# 07_DEBUG.net
KiCad netlist of a schematic drawn in Altium Designer
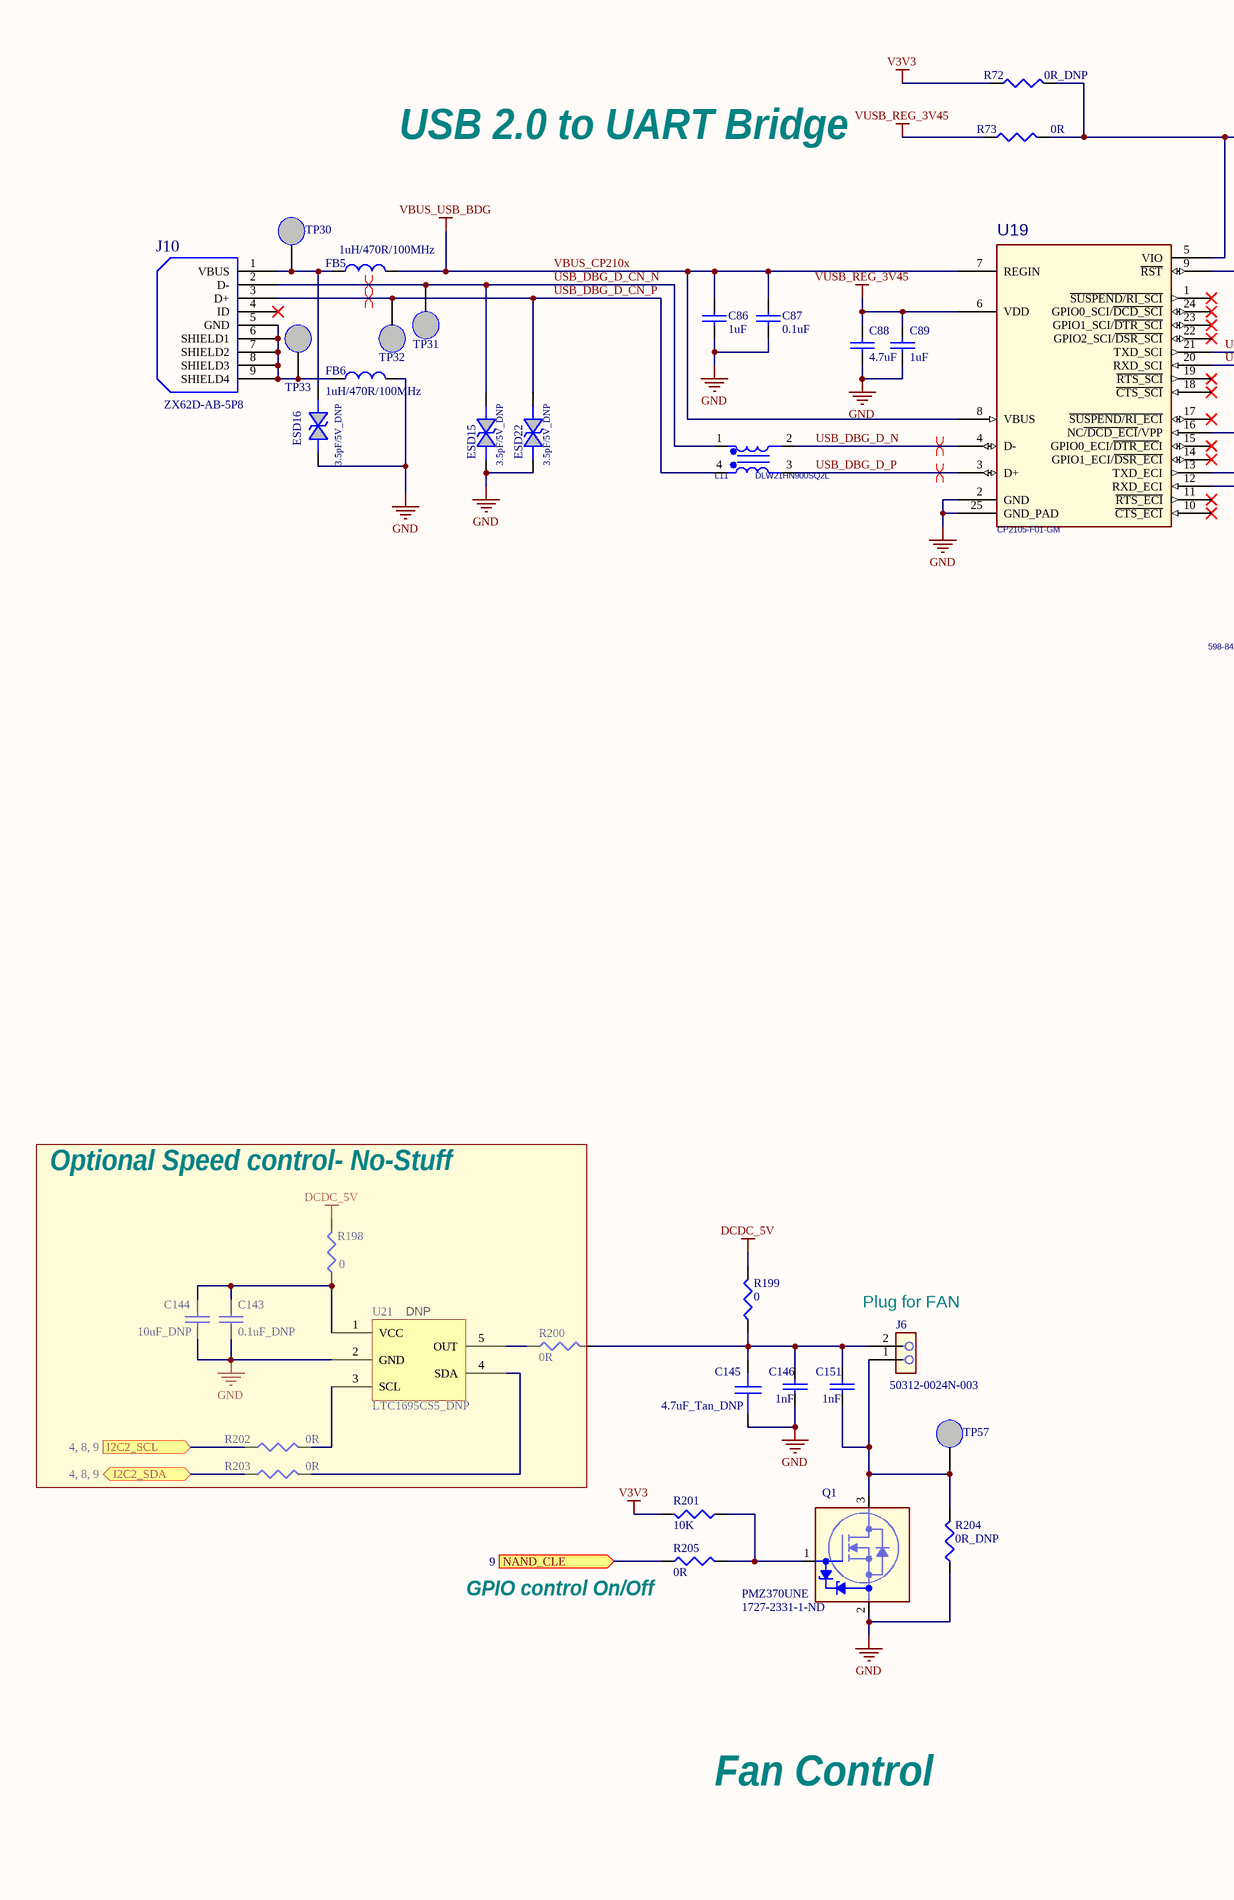
[diagram p0: 07_DEBUG.SchDoc, left]
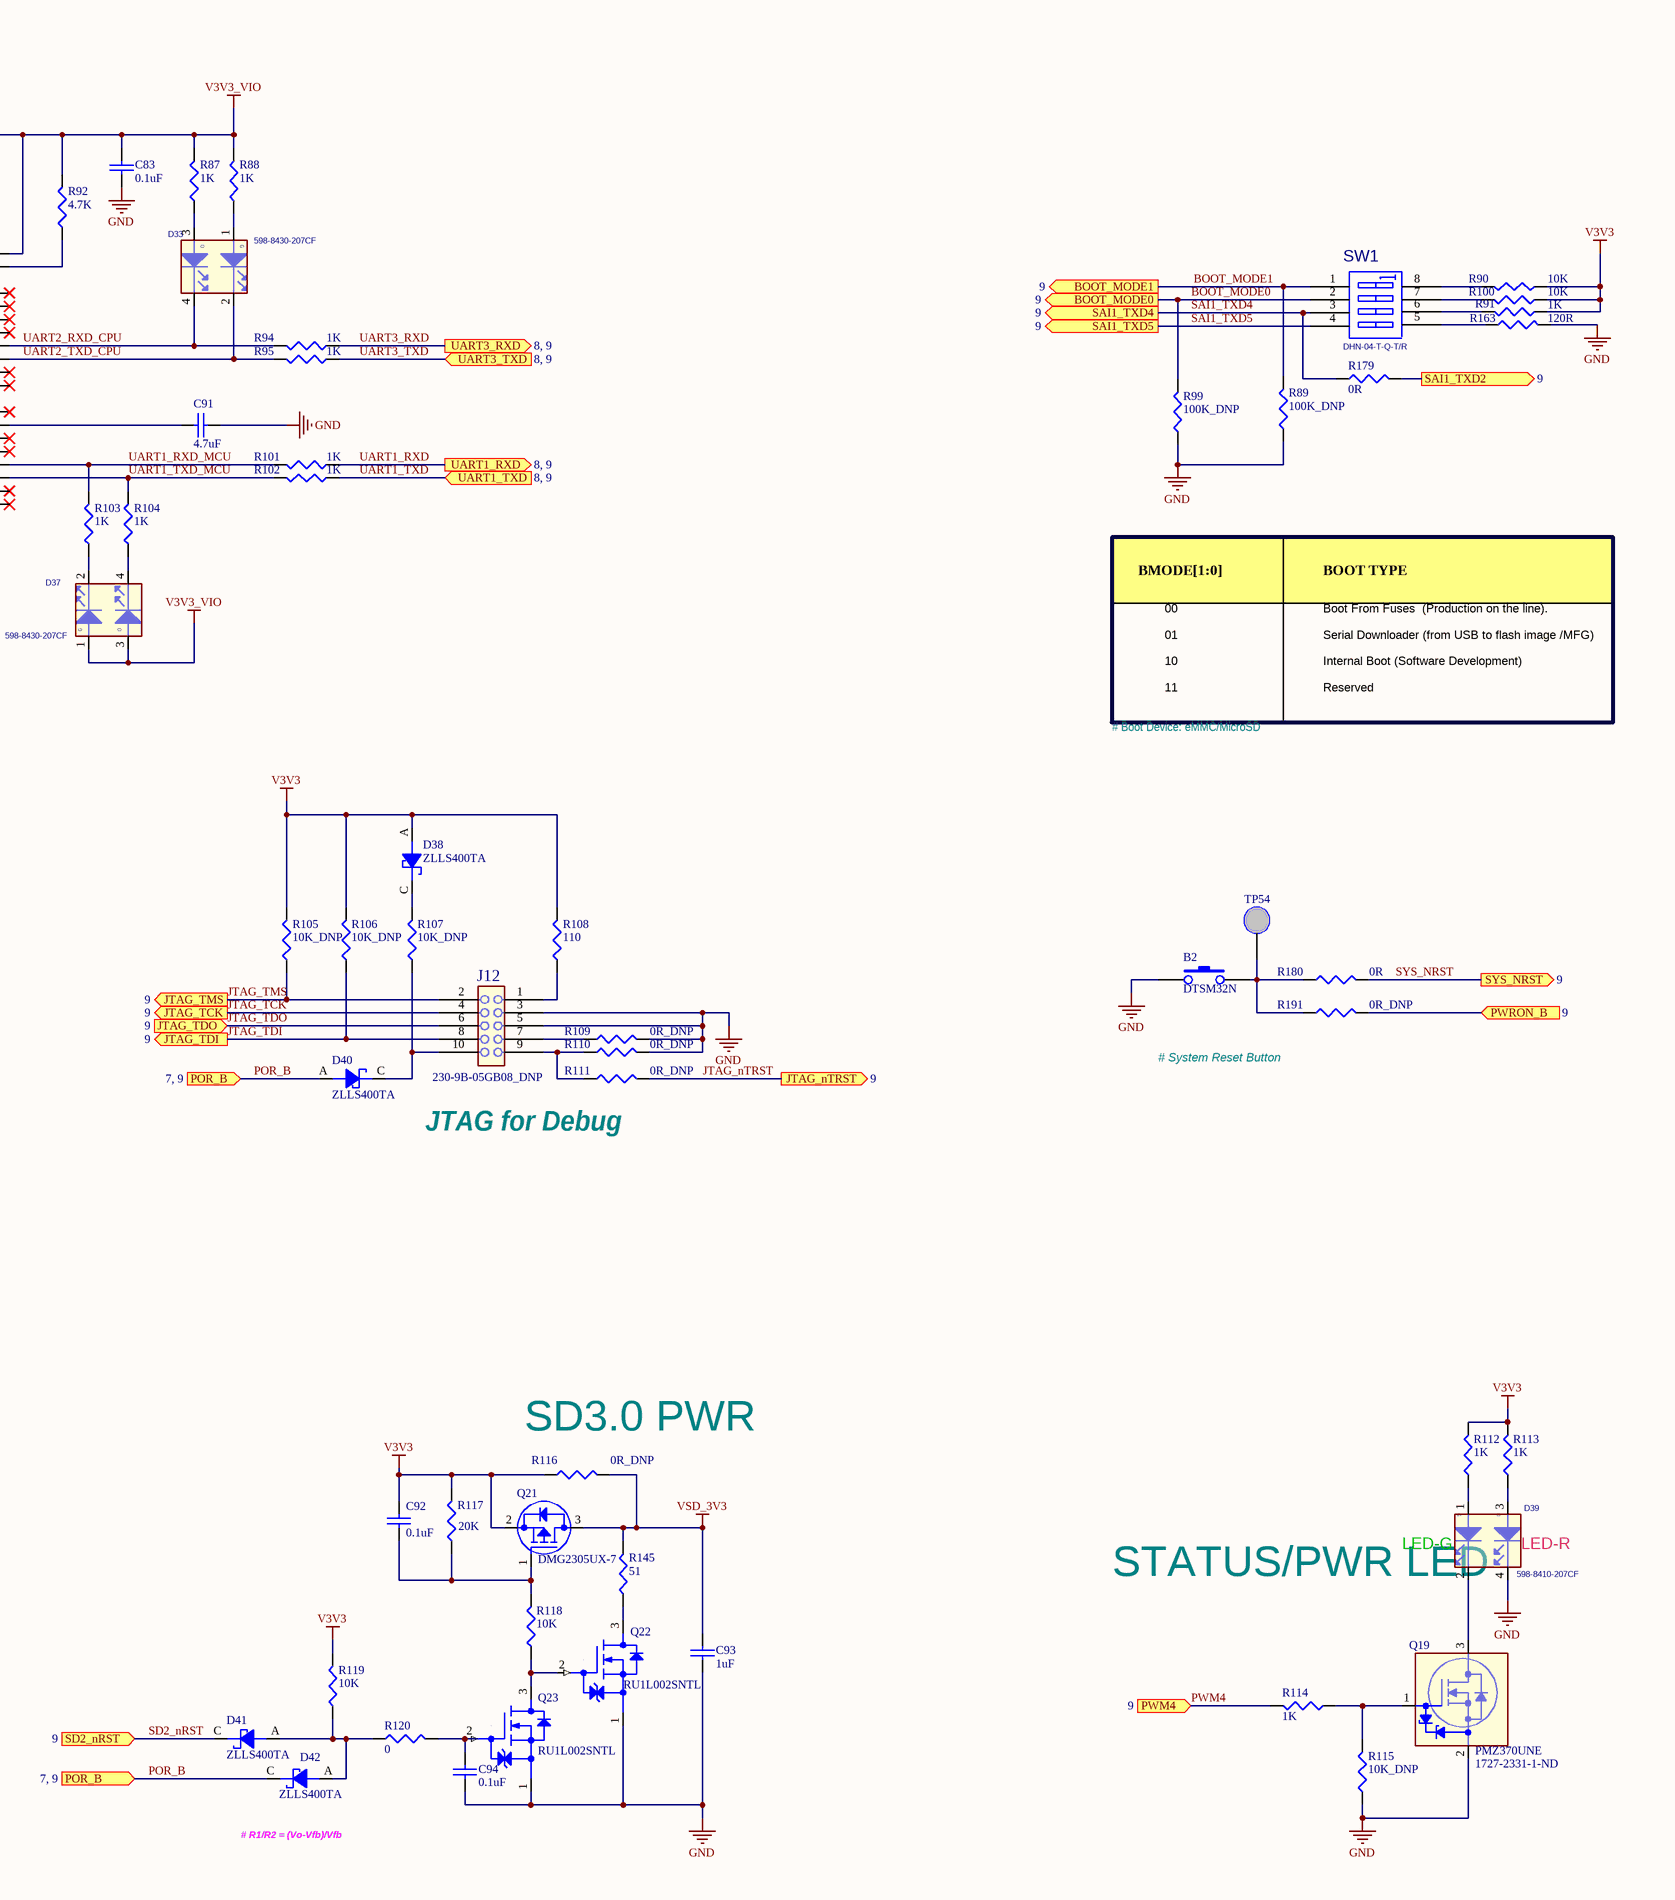
[diagram p1: 07_DEBUG.SchDoc, right]

(export (version "E")
  (design (tool "Eeschema 10.0.6"))
  (components
    (comp (ref "B2")
      (value "DTSM32N")
      (footprint "sw2-6_0x3_5-h5_2")
      (description "Tact Switch")
      (fields (field (name "MPN") "DTSM-32N-Q-TR"))
      (libsource (lib "links") (part "SW-PB"))
    )
    (comp (ref "C83")
      (value "0.1uF")
      (footprint "0201")
      (description "CAP CER 0.1UF 10V 10% X5R 0201")
      (fields (field (name "MPN") "C0603X5R1A104K030BC") (field (name "Comment") "0.1uF/10V"))
      (libsource (lib "links") (part "CAP_0201_0.1uF"))
    )
    (comp (ref "C86")
      (value "1uF")
      (footprint "0201")
      (description "CAP CER 1UF 6.3V 20% X5R 0201")
      (fields (field (name "MPN") "C0603X5R0J105M030BC") (field (name "Comment") "1uF/6.3V"))
      (libsource (lib "links") (part "CAP_0201_1.0uF"))
    )
    (comp (ref "C87")
      (value "0.1uF")
      (footprint "0201")
      (description "CAP CER 0.1UF 10V 10% X5R 0201")
      (fields (field (name "MPN") "C0603X5R1A104K030BC") (field (name "Comment") "0.1uF/10V"))
      (libsource (lib "links") (part "CAP_0201_0.1uF"))
    )
    (comp (ref "C88")
      (value "4.7uF")
      (footprint "0402")
      (description "CAP CER 4.7UF 10V 20% X5R 0402")
      (fields (field (name "MPN") "C1005X5R1A475M050BC") (field (name "Comment") "4.7uF/10V"))
      (libsource (lib "links") (part "CAP_0402_4.7uF"))
    )
    (comp (ref "C89")
      (value "1uF")
      (footprint "0201")
      (description "CAP CER 1UF 6.3V 20% X5R 0201")
      (fields (field (name "MPN") "C0603X5R0J105M030BC") (field (name "Comment") "1uF/6.3V"))
      (libsource (lib "links") (part "CAP_0201_1.0uF"))
    )
    (comp (ref "C91")
      (value "4.7uF")
      (footprint "0402")
      (description "CAP CER 4.7UF 10V 20% X5R 0402")
      (fields (field (name "MPN") "C1005X5R1A475M050BC") (field (name "Comment") "4.7uF/10V"))
      (libsource (lib "links") (part "CAP_0402_4.7uF"))
    )
    (comp (ref "C92")
      (value "0.1uF")
      (footprint "0201")
      (description "CAP CER 0.1UF 10V 10% X5R 0201")
      (fields (field (name "MPN") "C0603X5R1A104K030BC") (field (name "Comment") "0.1uF/10V"))
      (libsource (lib "links") (part "CAP_0201_0.1uF"))
    )
    (comp (ref "C93")
      (value "1uF")
      (footprint "0201")
      (description "CAP CER 1UF 6.3V 20% X5R 0201")
      (fields (field (name "MPN") "C0603X5R0J105M030BC") (field (name "Comment") "1uF/6.3V"))
      (libsource (lib "links") (part "CAP_0201_1.0uF"))
    )
    (comp (ref "C94")
      (value "0.1uF")
      (footprint "0201")
      (description "CAP CER 0.1UF 10V 10% X5R 0201")
      (fields (field (name "MPN") "C0603X5R1A104K030BC") (field (name "Comment") "0.1uF/10V"))
      (libsource (lib "links") (part "CAP_0201_0.1uF"))
    )
    (comp (ref "C143")
      (value "0.1uF_DNP")
      (footprint "0201")
      (description "CAP CER 0.1UF 10V 10% X5R 0201")
      (fields (field (name "MPN") "C0603X5R1A104K030BC") (field (name "Comment") "0.1uF/10V"))
      (libsource (lib "links") (part "CAP_0201_0.1uF"))
    )
    (comp (ref "C144")
      (value "10uF_DNP")
      (footprint "0402")
      (description "CAP CER 10UF 10V 20% X5R 0402")
      (fields (field (name "MPN") "CL05A106MP5NUNC") (field (name "Comment") "10uF/10V"))
      (libsource (lib "links") (part "CAP_0402_10uF"))
    )
    (comp (ref "C145")
      (value "4.7uF_Tan_DNP")
      (footprint "1206")
      (description "CAP CER 47UF 25V 20% 1206")
      (fields (field (name "MPN") "C3216JB1E476M160AC") (field (name "Comment") "47uF/25V"))
      (libsource (lib "links") (part "CAP_1206_47uF_25V"))
    )
    (comp (ref "C146")
      (value "1nF")
      (footprint "0201")
      (description "CAP CER 1nF 25V 10% X7R 0201")
      (fields (field (name "MPN") "GRM033R71E102KA01D") (field (name "Comment") "1nF/25V"))
      (libsource (lib "links") (part "CAP_0201_1.0nF"))
    )
    (comp (ref "C151")
      (value "1nF")
      (footprint "0201")
      (description "CAP CER 1nF 25V 10% X7R 0201")
      (fields (field (name "MPN") "GRM033R71E102KA01D") (field (name "Comment") "1nF/25V"))
      (libsource (lib "links") (part "CAP_0201_1.0nF"))
    )
    (comp (ref "D33")
      (value "598-8430-207CF")
      (footprint "LED_0606")
      (description "LED BI-COLOR ORANGE/GRN 20MA SMD 0606")
      (libsource (lib "") (part "LED4_DUAL_OG_1"))
    )
    (comp (ref "D37")
      (value "598-8430-207CF")
      (footprint "LED_0606")
      (description "LED BI-COLOR ORANGE/GRN 20MA SMD 0606")
      (libsource (lib "SpacePark") (part "LED4_DUAL_OG"))
    )
    (comp (ref "D38")
      (value "ZLLS400TA")
      (footprint "SOD323")
      (description "DIODE SCHOTTKY 40V 520MA SOD323")
      (libsource (lib "SpacePark") (part "DIODE_SCHTKY"))
    )
    (comp (ref "D39")
      (value "598-8410-207CF")
      (footprint "LED_0606")
      (description "LED BI-COLOR ORANGE/GRN 20MA SMD 0606")
      (fields (field (name "MPN") "598-8430-207CF"))
      (libsource (lib "") (part "LED4_DUAL_OG_2"))
    )
    (comp (ref "D40")
      (value "ZLLS400TA")
      (footprint "SOD323")
      (description "DIODE SCHOTTKY 40V 520MA SOD323")
      (libsource (lib "SpacePark") (part "DIODE_SCHTKY"))
    )
    (comp (ref "D41")
      (value "ZLLS400TA")
      (footprint "SOD323")
      (description "DIODE SCHOTTKY 40V 520MA SOD323")
      (libsource (lib "SpacePark") (part "DIODE_SCHTKY"))
    )
    (comp (ref "D42")
      (value "ZLLS400TA")
      (footprint "SOD323")
      (description "DIODE SCHOTTKY 40V 520MA SOD323")
      (libsource (lib "SpacePark") (part "DIODE_SCHTKY"))
    )
    (comp (ref "ESD15")
      (value "3.5pF/5V_DNP")
      (footprint "0201")
      (description "DIODE TVS 15kV 10V 50A 8pF SMT RoHS")
      (fields (field (name "MPN") "DESD5V0V1BCSP-7"))
      (libsource (lib "links") (part "DIODE BI-DIR TRIG"))
    )
    (comp (ref "ESD16")
      (value "3.5pF/5V_DNP")
      (footprint "0201")
      (description "DIODE TVS 15kV 10V 50A 8pF SMT RoHS")
      (fields (field (name "MPN") "DESD5V0V1BCSP-7"))
      (libsource (lib "links") (part "DIODE BI-DIR TRIG"))
    )
    (comp (ref "ESD22")
      (value "3.5pF/5V_DNP")
      (footprint "0201")
      (description "DIODE TVS 15kV 10V 50A 8pF SMT RoHS")
      (fields (field (name "MPN") "DESD5V0V1BCSP-7"))
      (libsource (lib "links") (part "DIODE BI-DIR TRIG"))
    )
    (comp (ref "FB5")
      (value "1uH/470R/100MHz")
      (footprint "0603")
      (description "FERRITE CHIP 470 OHM 1.0A 0603")
      (fields (field (name "MPN") "BLM18PG471SN1"))
      (libsource (lib "links") (part "INDUCTOR_BLM18PG471SN1"))
    )
    (comp (ref "FB6")
      (value "1uH/470R/100MHz")
      (footprint "0603")
      (description "FERRITE CHIP 470 OHM 1.0A 0603")
      (fields (field (name "MPN") "BLM18PG471SN1"))
      (libsource (lib "links") (part "INDUCTOR_BLM18PG471SN1"))
    )
    (comp (ref "J6")
      (value "50312-0024N-003")
      (footprint "SIP2-2MM-6X4_8MM-50312")
      (description "CONN DIP HEADER 2P 1R MS(P2.0,H6.2)")
      (libsource (lib "SBC") (part "HEADER 1X2"))
    )
    (comp (ref "J10")
      (value "ZX62D-AB-5P8")
      (footprint "USB5-0_65-ZX62D-AB-5P8")
      (description "Micro USB AB Connector, Standard SMT + DIP")
      (libsource (lib "links") (part "USB_AB"))
    )
    (comp (ref "J12")
      (value "230-9B-05GB08_DNP")
      (footprint "HD2X5-1_27MM-3_35MM")
      (description "2x5 pin header, 1.27mm pitch, THM")
      (fields (field (name "MPN") "230-9B-05GB08"))
      (libsource (lib "links") (part "HEADER 2x5"))
    )
    (comp (ref "L11")
      (value "DLW21HN900SQ2L")
      (footprint "IND4_CHOKE_0805")
      (description "IND CHK 90 OHM@100MHZ 330MA 25% 0805")
      (libsource (lib "SpacePark") (part "IND_CMC_DLW21"))
    )
    (comp (ref "Q1")
      (value "PMZ370UNE")
      (footprint "DFN10106B")
      (description "N-Channel 30V 590mA, SMT DFN1006B-3")
      (fields (field (name "SUPPLIER PART NUMBER 1") "1727-2331-1-ND") (field (name "MPN") "PMZB550UNEYL"))
      (libsource (lib "SpacePark") (part "NMOS_NX3008NBK"))
    )
    (comp (ref "Q19")
      (value "PMZ370UNE")
      (footprint "DFN10106B")
      (description "N-Channel 30V 590mA, SMT DFN1006B-3")
      (fields (field (name "SUPPLIER PART NUMBER 1") "1727-2331-1-ND") (field (name "MPN") "PMZB550UNEYL"))
      (libsource (lib "SpacePark") (part "NMOS_NX3008NBK"))
    )
    (comp (ref "Q21")
      (value "DMG2305UX-7")
      (footprint "SOT-23")
      (description "P-Channel 20V 4.2A (Ta) 1.4W (Ta) Surface Mount SOT-23")
      (libsource (lib "SpacePark") (part "MOSFET_P"))
    )
    (comp (ref "Q22")
      (value "RU1L002SNTL")
      (footprint "SOT323_3")
      (description "N-Channel 30V 100mA (Ta) 200mW (Ta) Surface Mount SOT-323")
      (fields (field (name "MPN") "SOT323_3"))
      (libsource (lib "SpacePark") (part "2SK3018"))
    )
    (comp (ref "Q23")
      (value "RU1L002SNTL")
      (footprint "SOT323_3")
      (description "N-Channel 30V 100mA (Ta) 200mW (Ta) Surface Mount SOT-323")
      (fields (field (name "MPN") "SOT323_3"))
      (libsource (lib "SpacePark") (part "2SK3018"))
    )
    (comp (ref "R72")
      (value "0R_DNP")
      (footprint "0201")
      (description "RES SMD 0.0OHM JUMPER 1/20W 0201")
      (fields (field (name "MPN") "ERJ-1GN0R00C"))
      (libsource (lib "links") (part "R_0201_0"))
    )
    (comp (ref "R73")
      (value "0R")
      (footprint "0201")
      (description "RES SMD 0.0OHM JUMPER 1/20W 0201")
      (fields (field (name "MPN") "ERJ-1GN0R00C"))
      (libsource (lib "links") (part "R_0201_0"))
    )
    (comp (ref "R87")
      (value "1K")
      (footprint "0201")
      (description "RES SMD 1K OHM 1% 1/20W 0201")
      (fields (field (name "MPN") "ERJ-1GEF1001C") (field (name "Comment") "1K/1%"))
      (libsource (lib "links") (part "R_0201_1K"))
    )
    (comp (ref "R88")
      (value "1K")
      (footprint "0201")
      (description "RES SMD 1K OHM 1% 1/20W 0201")
      (fields (field (name "MPN") "ERJ-1GEF1001C") (field (name "Comment") "1K/1%"))
      (libsource (lib "links") (part "R_0201_1K"))
    )
    (comp (ref "R89")
      (value "100K_DNP")
      (footprint "0201")
      (description "RES SMD 100K OHM JUMPER 1/20W  0201")
      (fields (field (name "MPN") "ERJ-1GEF1003C"))
      (libsource (lib "links") (part "R_0201_100K"))
    )
    (comp (ref "R90")
      (value "10K")
      (footprint "0201")
      (description "RES SMD 10K OHM JUMPER 1/20W  0201")
      (fields (field (name "MPN") "ERJ-1GEF103C"))
      (libsource (lib "links") (part "R_0201_10K"))
    )
    (comp (ref "R91")
      (value "1K")
      (footprint "0201")
      (description "RES SMD 1K OHM 1% 1/20W 0201")
      (fields (field (name "MPN") "ERJ-1GEF1001C") (field (name "Comment") "1K/1%"))
      (libsource (lib "links") (part "R_0201_1K"))
    )
    (comp (ref "R92")
      (value "4.7K")
      (footprint "0201")
      (description "RES SMD 4.7K OHM 1% 1/20W 0201")
      (fields (field (name "MPN") "ERJ-1GEF4701C"))
      (libsource (lib "links") (part "R_0201_4.7K"))
    )
    (comp (ref "R94")
      (value "1K")
      (footprint "0201")
      (description "RES SMD 1K OHM 1% 1/20W 0201")
      (fields (field (name "MPN") "ERJ-1GEF1001C") (field (name "Comment") "1K/1%"))
      (libsource (lib "links") (part "R_0201_1K"))
    )
    (comp (ref "R95")
      (value "1K")
      (footprint "0201")
      (description "RES SMD 1K OHM 1% 1/20W 0201")
      (fields (field (name "MPN") "ERJ-1GEF1001C") (field (name "Comment") "1K/1%"))
      (libsource (lib "links") (part "R_0201_1K"))
    )
    (comp (ref "R99")
      (value "100K_DNP")
      (footprint "0201")
      (description "RES SMD 100K OHM JUMPER 1/20W  0201")
      (fields (field (name "MPN") "ERJ-1GEF1003C"))
      (libsource (lib "links") (part "R_0201_100K"))
    )
    (comp (ref "R100")
      (value "10K")
      (footprint "0201")
      (description "RES SMD 10K OHM JUMPER 1/20W  0201")
      (fields (field (name "MPN") "ERJ-1GEF103C"))
      (libsource (lib "links") (part "R_0201_10K"))
    )
    (comp (ref "R101")
      (value "1K")
      (footprint "0201")
      (description "RES SMD 1K OHM 1% 1/20W 0201")
      (fields (field (name "MPN") "ERJ-1GEF1001C") (field (name "Comment") "1K/1%"))
      (libsource (lib "links") (part "R_0201_1K"))
    )
    (comp (ref "R102")
      (value "1K")
      (footprint "0201")
      (description "RES SMD 1K OHM 1% 1/20W 0201")
      (fields (field (name "MPN") "ERJ-1GEF1001C") (field (name "Comment") "1K/1%"))
      (libsource (lib "links") (part "R_0201_1K"))
    )
    (comp (ref "R103")
      (value "1K")
      (footprint "0201")
      (description "RES SMD 1K OHM 1% 1/20W 0201")
      (fields (field (name "MPN") "ERJ-1GEF1001C") (field (name "Comment") "1K/1%"))
      (libsource (lib "links") (part "R_0201_1K"))
    )
    (comp (ref "R104")
      (value "1K")
      (footprint "0201")
      (description "RES SMD 1K OHM 1% 1/20W 0201")
      (fields (field (name "MPN") "ERJ-1GEF1001C") (field (name "Comment") "1K/1%"))
      (libsource (lib "links") (part "R_0201_1K"))
    )
    (comp (ref "R105")
      (value "10K_DNP")
      (footprint "0201")
      (description "RES SMD 10K OHM JUMPER 1/20W  0201")
      (fields (field (name "MPN") "ERJ-1GEF103C"))
      (libsource (lib "links") (part "R_0201_10K"))
    )
    (comp (ref "R106")
      (value "10K_DNP")
      (footprint "0201")
      (description "RES SMD 10K OHM JUMPER 1/20W  0201")
      (fields (field (name "MPN") "ERJ-1GEF103C"))
      (libsource (lib "links") (part "R_0201_10K"))
    )
    (comp (ref "R107")
      (value "10K_DNP")
      (footprint "0201")
      (description "RES SMD 10K OHM JUMPER 1/20W  0201")
      (fields (field (name "MPN") "ERJ-1GEF103C"))
      (libsource (lib "links") (part "R_0201_10K"))
    )
    (comp (ref "R108")
      (value "110")
      (footprint "0201")
      (description "RES SMD 110 OHM 1% 1/20W 0201")
      (fields (field (name "MPN") "ERJ-1GEF1100C"))
      (libsource (lib "links") (part "R_0201_110"))
    )
    (comp (ref "R109")
      (value "0R_DNP")
      (footprint "0201")
      (description "RES SMD 0.0OHM JUMPER 1/20W 0201")
      (fields (field (name "MPN") "ERJ-1GN0R00C"))
      (libsource (lib "links") (part "R_0201_0"))
    )
    (comp (ref "R110")
      (value "0R_DNP")
      (footprint "0201")
      (description "RES SMD 0.0OHM JUMPER 1/20W 0201")
      (fields (field (name "MPN") "ERJ-1GN0R00C"))
      (libsource (lib "links") (part "R_0201_0"))
    )
    (comp (ref "R111")
      (value "0R_DNP")
      (footprint "0201")
      (description "RES SMD 0.0OHM JUMPER 1/20W 0201")
      (fields (field (name "MPN") "ERJ-1GN0R00C"))
      (libsource (lib "links") (part "R_0201_0"))
    )
    (comp (ref "R112")
      (value "1K")
      (footprint "0201")
      (description "RES SMD 1K OHM 1% 1/20W 0201")
      (fields (field (name "MPN") "ERJ-1GEF1001C") (field (name "Comment") "1K/1%"))
      (libsource (lib "links") (part "R_0201_1K"))
    )
    (comp (ref "R113")
      (value "1K")
      (footprint "0201")
      (description "RES SMD 1K OHM 1% 1/20W 0201")
      (fields (field (name "MPN") "ERJ-1GEF1001C") (field (name "Comment") "1K/1%"))
      (libsource (lib "links") (part "R_0201_1K"))
    )
    (comp (ref "R114")
      (value "1K")
      (footprint "0201")
      (description "RES SMD 1K OHM 1% 1/20W 0201")
      (fields (field (name "MPN") "ERJ-1GEF1001C") (field (name "Comment") "1K/1%"))
      (libsource (lib "links") (part "R_0201_1K"))
    )
    (comp (ref "R115")
      (value "10K_DNP")
      (footprint "0201")
      (description "RES SMD 10K OHM JUMPER 1/20W  0201")
      (fields (field (name "MPN") "ERJ-1GEF103C"))
      (libsource (lib "links") (part "R_0201_10K"))
    )
    (comp (ref "R116")
      (value "0R_DNP")
      (footprint "0402")
      (description "RES SMD 0.0 OHM JUMPER 1/10W  0402")
      (fields (field (name "MPN") "ERJ-2GE0R00X"))
      (libsource (lib "links") (part "R_0402_0"))
    )
    (comp (ref "R117")
      (value "20K")
      (footprint "0201")
      (description "RES SMD 20K OHM 1% 1/20W 0201")
      (fields (field (name "MPN") "ERJ-1GEF2002C"))
      (libsource (lib "links") (part "R_0201_20K"))
    )
    (comp (ref "R118")
      (value "10K")
      (footprint "0201")
      (description "RES SMD 10K OHM JUMPER 1/20W  0201")
      (fields (field (name "MPN") "ERJ-1GEF103C"))
      (libsource (lib "links") (part "R_0201_10K"))
    )
    (comp (ref "R119")
      (value "10K")
      (footprint "0201")
      (description "RES SMD 10K OHM JUMPER 1/20W  0201")
      (fields (field (name "MPN") "ERJ-1GEF103C"))
      (libsource (lib "links") (part "R_0201_10K"))
    )
    (comp (ref "R120")
      (value "0")
      (footprint "0402")
      (description "RES SMD 0.0 OHM JUMPER 1/10W  0402")
      (fields (field (name "MPN") "ERJ-2GE0R00X") (field (name "Comment") "0R"))
      (libsource (lib "links") (part "R_0402_0"))
    )
    (comp (ref "R145")
      (value "51")
      (footprint "0402")
      (description "RES SMD 51 OHM 1% 1/10W 0402")
      (fields (field (name "MPN") "ERJ-2RKF51R0X"))
      (libsource (lib "links") (part "R_0402_51"))
    )
    (comp (ref "R163")
      (value "120R")
      (footprint "0402")
      (description "RES SMD 120 OHM 1% 1/10W 0402")
      (fields (field (name "MPN") "RC0402FR-07120R"))
      (libsource (lib "links") (part "R_0402_120"))
    )
    (comp (ref "R179")
      (value "0R")
      (footprint "0201")
      (description "RES SMD 0.0OHM JUMPER 1/20W 0201")
      (fields (field (name "MPN") "ERJ-1GN0R00C"))
      (libsource (lib "links") (part "R_0805_0"))
    )
    (comp (ref "R180")
      (value "0R")
      (footprint "0201")
      (description "RES SMD 0.0OHM JUMPER 1/20W 0201")
      (fields (field (name "MPN") "ERJ-1GN0R00C") (field (name "Comment") "0R_DNP"))
      (libsource (lib "links") (part "R_0201_0"))
    )
    (comp (ref "R191")
      (value "0R_DNP")
      (footprint "0201")
      (description "RES SMD 0.0OHM JUMPER 1/20W 0201")
      (fields (field (name "MPN") "ERJ-1GN0R00C"))
      (libsource (lib "links") (part "R_0201_0"))
    )
    (comp (ref "R198")
      (value "0")
      (footprint "0402")
      (description "RES SMD 0.0 OHM JUMPER 1/10W  0402")
      (fields (field (name "MPN") "ERJ-2GE0R00X") (field (name "Comment") "0R"))
      (libsource (lib "links") (part "R_0402_0"))
    )
    (comp (ref "R199")
      (value "0")
      (footprint "0402")
      (description "RES SMD 0.0 OHM JUMPER 1/10W  0402")
      (fields (field (name "MPN") "ERJ-2GE0R00X") (field (name "Comment") "0R"))
      (libsource (lib "links") (part "R_0402_0"))
    )
    (comp (ref "R200")
      (value "0R")
      (footprint "0402")
      (description "RES SMD 0.0 OHM JUMPER 1/10W  0402")
      (fields (field (name "MPN") "ERJ-2GE0R00X"))
      (libsource (lib "links") (part "R_0402_0"))
    )
    (comp (ref "R201")
      (value "10K")
      (footprint "0201")
      (description "RES SMD 10K OHM JUMPER 1/20W  0201")
      (fields (field (name "MPN") "ERJ-1GEF103C"))
      (libsource (lib "links") (part "R_0201_10K"))
    )
    (comp (ref "R202")
      (value "0R")
      (footprint "0201")
      (description "RES SMD 0.0OHM JUMPER 1/20W 0201")
      (fields (field (name "MPN") "ERJ-1GN0R00C") (field (name "Comment") "0"))
      (libsource (lib "links") (part "R_0201_0"))
    )
    (comp (ref "R203")
      (value "0R")
      (footprint "0201")
      (description "RES SMD 0.0OHM JUMPER 1/20W 0201")
      (fields (field (name "MPN") "ERJ-1GN0R00C") (field (name "Comment") "0"))
      (libsource (lib "links") (part "R_0201_0"))
    )
    (comp (ref "R204")
      (value "0R_DNP")
      (footprint "0402")
      (description "RES SMD 0.0 OHM JUMPER 1/10W  0402")
      (fields (field (name "MPN") "ERJ-2GE0R00X") (field (name "Comment") "0R"))
      (libsource (lib "links") (part "R_0402_0"))
    )
    (comp (ref "R205")
      (value "0R")
      (footprint "0201")
      (description "RES SMD 0.0OHM JUMPER 1/20W 0201")
      (fields (field (name "MPN") "ERJ-1GN0R00C") (field (name "Comment") "0R_DNP"))
      (libsource (lib "links") (part "R_0201_0"))
    )
    (comp (ref "SW1")
      (value "DHN-04-T-Q-T/R")
      (footprint "SW_DIP4_SM")
      (description "SW 4P SPST DIP 25MA 24V SMT")
      (libsource (lib "SpacePark") (part "SW_DIP-4"))
    )
    (comp (ref "TP30")
      (value "TP NM")
      (footprint "TP_SMD_L")
      (description "TEST POINT (Large)")
      (libsource (lib "links") (part "TP_L"))
    )
    (comp (ref "TP31")
      (value "TP NM")
      (footprint "TP_SMD")
      (description "TEST POIN")
      (libsource (lib "links") (part "TP"))
    )
    (comp (ref "TP32")
      (value "TP NM")
      (footprint "TP_SMD")
      (description "TEST POIN")
      (libsource (lib "links") (part "TP"))
    )
    (comp (ref "TP33")
      (value "TP NM")
      (footprint "TP_SMD_L")
      (description "TEST POINT (Large)")
      (libsource (lib "links") (part "TP_L"))
    )
    (comp (ref "TP54")
      (value "TP NM")
      (footprint "TP_SMD_L")
      (description "TEST POINT (Large)")
      (libsource (lib "links") (part "TP_L"))
    )
    (comp (ref "TP57")
      (value "TP NM")
      (footprint "TP_SMD_L")
      (description "TEST POINT (Large)")
      (libsource (lib "links") (part "TP_L"))
    )
    (comp (ref "U19")
      (value "CP2105-F01-GM")
      (footprint "QFN24_0P5_4X4_EP")
      (description "IC XCVR USB TO DUAL-UART 3.0-3.6V QFN24")
      (libsource (lib "SpacePark") (part "CP2105_QFN24P"))
    )
    (comp (ref "U21")
      (value "LTC1695CS5_DNP")
      (footprint "SOT23-S5-1695f")
      (description "LTC1695CS5")
      (libsource (lib "Schlib1") (part "LTC1695"))
    )
  )
  (nets
    (net (code "1") (name "/BOOT_MODE0") (class "Default")
      (node (ref "R99") (pin "2") (pintype "passive"))
      (node (ref "SW1") (pin "2") (pinfunction "A2_2") (pintype "passive"))
    )
    (net (code "2") (name "/BOOT_MODE1") (class "Default")
      (node (ref "R89") (pin "2") (pintype "passive"))
      (node (ref "SW1") (pin "1") (pinfunction "A1_1") (pintype "passive"))
    )
    (net (code "3") (name "/I2C2_SCL") (class "Default") (node (ref "R202") (pin "1") (pintype "passive")))
    (net (code "4") (name "/I2C2_SDA") (class "Default") (node (ref "R203") (pin "1") (pintype "passive")))
    (net (code "5") (name "/JTAG_TCK") (class "Default")
      (node (ref "J12") (pin "4") (pinfunction "4_4") (pintype "passive"))
    )
    (net (code "6") (name "/JTAG_TDI") (class "Default")
      (node (ref "J12") (pin "8") (pinfunction "8_8") (pintype "passive"))
      (node (ref "R106") (pin "1") (pintype "passive"))
    )
    (net (code "7") (name "/JTAG_TDO") (class "Default")
      (node (ref "J12") (pin "6") (pinfunction "6_6") (pintype "passive"))
    )
    (net (code "8") (name "/JTAG_TMS") (class "Default")
      (node (ref "J12") (pin "2") (pinfunction "2_2") (pintype "passive"))
      (node (ref "R105") (pin "1") (pintype "passive"))
    )
    (net (code "9") (name "/JTAG_nTRST") (class "Default") (node (ref "R111") (pin "2") (pintype "passive")))
    (net (code "10") (name "/NAND_CLE") (class "Default") (node (ref "R205") (pin "1") (pintype "passive")))
    (net (code "11") (name "/POR_B") (class "Default")
      (node (ref "D40") (pin "A") (pinfunction "A_A") (pintype "passive"))
      (node (ref "D42") (pin "C") (pinfunction "C_C") (pintype "passive"))
    )
    (net (code "12") (name "/PWM4") (class "Default") (node (ref "R114") (pin "2") (pintype "passive")))
    (net (code "13") (name "/PWRON_B") (class "Default") (node (ref "R191") (pin "2") (pintype "passive")))
    (net (code "14") (name "/SAI1_TXD2") (class "Default") (node (ref "R179") (pin "2") (pintype "passive")))
    (net (code "15") (name "/SAI1_TXD4") (class "Default")
      (node (ref "R179") (pin "1") (pintype "passive"))
      (node (ref "SW1") (pin "3") (pinfunction "A3_3") (pintype "passive"))
    )
    (net (code "16") (name "/SAI1_TXD5") (class "Default")
      (node (ref "SW1") (pin "4") (pinfunction "A4_4") (pintype "passive"))
    )
    (net (code "17") (name "/SD2_nRST") (class "Default")
      (node (ref "D41") (pin "C") (pinfunction "C_C") (pintype "passive"))
    )
    (net (code "18") (name "/SYS_NRST") (class "Default") (node (ref "R180") (pin "2") (pintype "passive")))
    (net (code "19") (name "/UART1_RXD") (class "Default") (node (ref "R101") (pin "1") (pintype "passive")))
    (net (code "20") (name "/UART1_RXD_MCU") (class "Default")
      (node (ref "R101") (pin "2") (pintype "passive"))
      (node (ref "R103") (pin "2") (pintype "passive"))
      (node (ref "U19") (pin "13") (pinfunction "TXD_ECI_13") (pintype "output"))
    )
    (net (code "21") (name "/UART1_TXD") (class "Default") (node (ref "R102") (pin "1") (pintype "passive")))
    (net (code "22") (name "/UART1_TXD_MCU") (class "Default")
      (node (ref "R102") (pin "2") (pintype "passive"))
      (node (ref "R104") (pin "2") (pintype "passive"))
      (node (ref "U19") (pin "12") (pinfunction "RXD_ECI_12") (pintype "input"))
    )
    (net (code "23") (name "/UART2_RXD_CPU") (class "Default")
      (node (ref "D33") (pin "4") (pinfunction "CATHODE2_4") (pintype "passive"))
      (node (ref "R94") (pin "2") (pintype "passive"))
      (node (ref "U19") (pin "21") (pinfunction "TXD_SCI_21") (pintype "output"))
    )
    (net (code "24") (name "/UART2_TXD_CPU") (class "Default")
      (node (ref "D33") (pin "2") (pinfunction "CATHODE1_2") (pintype "passive"))
      (node (ref "R95") (pin "2") (pintype "passive"))
      (node (ref "U19") (pin "20") (pinfunction "RXD_SCI_20") (pintype "input"))
    )
    (net (code "25") (name "/UART3_RXD") (class "Default") (node (ref "R94") (pin "1") (pintype "passive")))
    (net (code "26") (name "/UART3_TXD") (class "Default") (node (ref "R95") (pin "1") (pintype "passive")))
    (net (code "27") (name "/USB_DBG_D_CN_N") (class "Default")
      (node (ref "ESD15") (pin "2") (pinfunction "2_2") (pintype "passive"))
      (node (ref "J10") (pin "2") (pinfunction "D-_2") (pintype "passive"))
      (node (ref "L11") (pin "1") (pinfunction "1_1") (pintype "passive"))
      (node (ref "TP31") (pin "1") (pinfunction "1_1") (pintype "passive"))
    )
    (net (code "28") (name "/USB_DBG_D_CN_P") (class "Default")
      (node (ref "ESD22") (pin "2") (pinfunction "2_2") (pintype "passive"))
      (node (ref "J10") (pin "3") (pinfunction "D+_3") (pintype "passive"))
      (node (ref "L11") (pin "4") (pinfunction "4_4") (pintype "passive"))
      (node (ref "TP32") (pin "1") (pinfunction "1_1") (pintype "passive"))
    )
    (net (code "29") (name "/USB_DBG_D_N") (class "Default")
      (node (ref "L11") (pin "2") (pinfunction "2_2") (pintype "passive"))
      (node (ref "U19") (pin "4") (pinfunction "D-_4") (pintype "bidirectional"))
    )
    (net (code "30") (name "/USB_DBG_D_P") (class "Default")
      (node (ref "L11") (pin "3") (pinfunction "3_3") (pintype "passive"))
      (node (ref "U19") (pin "3") (pinfunction "D+_3") (pintype "bidirectional"))
    )
    (net (code "31") (name "DCDC_5V") (class "Default")
      (node (ref "R198") (pin "2") (pintype "passive"))
      (node (ref "R199") (pin "2") (pintype "passive"))
    )
    (net (code "32") (name "GND") (class "Default")
      (node (ref "B2") (pin "1") (pinfunction "1_1") (pintype "passive"))
      (node (ref "C143") (pin "2") (pinfunction "2_2") (pintype "passive"))
      (node (ref "C144") (pin "2") (pinfunction "2_2") (pintype "passive"))
      (node (ref "C145") (pin "2") (pinfunction "2_2") (pintype "passive"))
      (node (ref "C146") (pin "1") (pinfunction "1_1") (pintype "passive"))
      (node (ref "C83") (pin "2") (pinfunction "2_2") (pintype "passive"))
      (node (ref "C86") (pin "2") (pinfunction "2_2") (pintype "passive"))
      (node (ref "C87") (pin "2") (pinfunction "2_2") (pintype "passive"))
      (node (ref "C88") (pin "2") (pinfunction "2_2") (pintype "passive"))
      (node (ref "C89") (pin "2") (pinfunction "2_2") (pintype "passive"))
      (node (ref "C91") (pin "2") (pinfunction "2_2") (pintype "passive"))
      (node (ref "C93") (pin "2") (pinfunction "2_2") (pintype "passive"))
      (node (ref "C94") (pin "2") (pinfunction "2_2") (pintype "passive"))
      (node (ref "D39") (pin "4") (pinfunction "CATHODE2_4") (pintype "passive"))
      (node (ref "ESD15") (pin "1") (pinfunction "1_1") (pintype "passive"))
      (node (ref "ESD16") (pin "1") (pinfunction "1_1") (pintype "passive"))
      (node (ref "ESD22") (pin "1") (pinfunction "1_1") (pintype "passive"))
      (node (ref "FB6") (pin "2") (pinfunction "2_2") (pintype "passive"))
      (node (ref "J12") (pin "3") (pinfunction "3_3") (pintype "passive"))
      (node (ref "J12") (pin "5") (pinfunction "5_5") (pintype "passive"))
      (node (ref "Q1") (pin "2") (pinfunction "SOURCE_2") (pintype "passive"))
      (node (ref "Q19") (pin "2") (pinfunction "SOURCE_2") (pintype "passive"))
      (node (ref "Q22") (pin "1") (pinfunction "SOURCE_1") (pintype "passive"))
      (node (ref "Q23") (pin "1") (pinfunction "SOURCE_1") (pintype "passive"))
      (node (ref "R109") (pin "2") (pintype "passive"))
      (node (ref "R110") (pin "2") (pintype "passive"))
      (node (ref "R115") (pin "1") (pintype "passive"))
      (node (ref "R163") (pin "2") (pintype "passive"))
      (node (ref "R204") (pin "1") (pintype "passive"))
      (node (ref "R89") (pin "1") (pintype "passive"))
      (node (ref "R99") (pin "1") (pintype "passive"))
      (node (ref "U19") (pin "2") (pinfunction "GND_2") (pintype "power_in"))
      (node (ref "U19") (pin "25") (pinfunction "GND_PAD_25") (pintype "power_in"))
      (node (ref "U21") (pin "2") (pinfunction "GND_2") (pintype "power_in"))
    )
    (net (code "33") (name "Net-(B2-Pad2)") (class "Default")
      (node (ref "B2") (pin "2") (pinfunction "2_2") (pintype "passive"))
      (node (ref "R180") (pin "1") (pintype "passive"))
      (node (ref "R191") (pin "1") (pintype "passive"))
      (node (ref "TP54") (pin "1") (pinfunction "1_1") (pintype "passive"))
    )
    (net (code "34") (name "Net-(C145-Pad1)") (class "Default")
      (node (ref "C145") (pin "1") (pinfunction "1_1") (pintype "passive"))
      (node (ref "C146") (pin "2") (pinfunction "2_2") (pintype "passive"))
      (node (ref "C151") (pin "2") (pinfunction "2_2") (pintype "passive"))
      (node (ref "J6") (pin "2") (pinfunction "2_2") (pintype "passive"))
      (node (ref "R199") (pin "1") (pintype "passive"))
      (node (ref "R200") (pin "2") (pintype "passive"))
    )
    (net (code "35") (name "Net-(D33-ANODE1)") (class "Default")
      (node (ref "D33") (pin "1") (pinfunction "ANODE1_1") (pintype "passive"))
      (node (ref "R88") (pin "1") (pintype "passive"))
    )
    (net (code "36") (name "Net-(D33-ANODE2)") (class "Default")
      (node (ref "D33") (pin "3") (pinfunction "ANODE2_3") (pintype "passive"))
      (node (ref "R87") (pin "1") (pintype "passive"))
    )
    (net (code "37") (name "Net-(D37-CATHODE1)") (class "Default")
      (node (ref "D37") (pin "2") (pinfunction "CATHODE1_2") (pintype "passive"))
      (node (ref "R103") (pin "1") (pintype "passive"))
    )
    (net (code "38") (name "Net-(D37-CATHODE2)") (class "Default")
      (node (ref "D37") (pin "4") (pinfunction "CATHODE2_4") (pintype "passive"))
      (node (ref "R104") (pin "1") (pintype "passive"))
    )
    (net (code "39") (name "Net-(D38-PadC)") (class "Default")
      (node (ref "D38") (pin "C") (pinfunction "C_C") (pintype "passive"))
      (node (ref "R107") (pin "2") (pintype "passive"))
    )
    (net (code "40") (name "Net-(D39-ANODE1)") (class "Default")
      (node (ref "D39") (pin "1") (pinfunction "ANODE1_1") (pintype "passive"))
      (node (ref "R112") (pin "1") (pintype "passive"))
    )
    (net (code "41") (name "Net-(D39-ANODE2)") (class "Default")
      (node (ref "D39") (pin "3") (pinfunction "ANODE2_3") (pintype "passive"))
      (node (ref "R113") (pin "1") (pintype "passive"))
    )
    (net (code "42") (name "Net-(D39-CATHODE1)") (class "Default")
      (node (ref "D39") (pin "2") (pinfunction "CATHODE1_2") (pintype "passive"))
      (node (ref "Q19") (pin "3") (pinfunction "DRAIN_3") (pintype "passive"))
    )
    (net (code "43") (name "Net-(D40-PadC)") (class "Default")
      (node (ref "D40") (pin "C") (pinfunction "C_C") (pintype "passive"))
      (node (ref "J12") (pin "10") (pinfunction "10_10") (pintype "passive"))
      (node (ref "R107") (pin "1") (pintype "passive"))
    )
    (net (code "44") (name "Net-(D41-PadA)") (class "Default")
      (node (ref "D41") (pin "A") (pinfunction "A_A") (pintype "passive"))
      (node (ref "D42") (pin "A") (pinfunction "A_A") (pintype "passive"))
      (node (ref "R119") (pin "1") (pintype "passive"))
      (node (ref "R120") (pin "1") (pintype "passive"))
    )
    (net (code "45") (name "Net-(J10-GND)") (class "Default")
      (node (ref "FB6") (pin "1") (pinfunction "1_1") (pintype "passive"))
      (node (ref "J10") (pin "5") (pinfunction "GND_5") (pintype "passive"))
      (node (ref "J10") (pin "6") (pinfunction "SHIELD1_6") (pintype "passive"))
      (node (ref "J10") (pin "7") (pinfunction "SHIELD2_7") (pintype "passive"))
      (node (ref "J10") (pin "8") (pinfunction "SHIELD3_8") (pintype "passive"))
      (node (ref "J10") (pin "9") (pinfunction "SHIELD4_9") (pintype "passive"))
      (node (ref "TP33") (pin "1") (pinfunction "1_1") (pintype "passive"))
    )
    (net (code "46") (name "Net-(J10-VBUS)") (class "Default")
      (node (ref "ESD16") (pin "2") (pinfunction "2_2") (pintype "passive"))
      (node (ref "FB5") (pin "1") (pinfunction "1_1") (pintype "passive"))
      (node (ref "J10") (pin "1") (pinfunction "VBUS_1") (pintype "passive"))
      (node (ref "TP30") (pin "1") (pinfunction "1_1") (pintype "passive"))
    )
    (net (code "47") (name "Net-(J12-Pad1)") (class "Default")
      (node (ref "J12") (pin "1") (pinfunction "1_1") (pintype "passive"))
      (node (ref "R108") (pin "1") (pintype "passive"))
    )
    (net (code "48") (name "Net-(J12-Pad7)") (class "Default")
      (node (ref "J12") (pin "7") (pinfunction "7_7") (pintype "passive"))
      (node (ref "R109") (pin "1") (pintype "passive"))
    )
    (net (code "49") (name "Net-(J12-Pad9)") (class "Default")
      (node (ref "J12") (pin "9") (pinfunction "9_9") (pintype "passive"))
      (node (ref "R110") (pin "1") (pintype "passive"))
      (node (ref "R111") (pin "1") (pintype "passive"))
    )
    (net (code "50") (name "Net-(Q1-DRAIN)") (class "Default")
      (node (ref "C151") (pin "1") (pinfunction "1_1") (pintype "passive"))
      (node (ref "J6") (pin "1") (pinfunction "1_1") (pintype "passive"))
      (node (ref "Q1") (pin "3") (pinfunction "DRAIN_3") (pintype "passive"))
      (node (ref "R204") (pin "2") (pintype "passive"))
      (node (ref "TP57") (pin "1") (pinfunction "1_1") (pintype "passive"))
    )
    (net (code "51") (name "Net-(Q1-GATE)") (class "Default")
      (node (ref "Q1") (pin "1") (pinfunction "GATE_1") (pintype "passive"))
      (node (ref "R201") (pin "1") (pintype "passive"))
      (node (ref "R205") (pin "2") (pintype "passive"))
    )
    (net (code "52") (name "Net-(Q19-GATE)") (class "Default")
      (node (ref "Q19") (pin "1") (pinfunction "GATE_1") (pintype "passive"))
      (node (ref "R114") (pin "1") (pintype "passive"))
      (node (ref "R115") (pin "2") (pintype "passive"))
    )
    (net (code "53") (name "Net-(Q21-GATE)") (class "Default")
      (node (ref "C92") (pin "2") (pinfunction "2_2") (pintype "passive"))
      (node (ref "Q21") (pin "1") (pinfunction "GATE_1") (pintype "passive"))
      (node (ref "R117") (pin "1") (pintype "passive"))
      (node (ref "R118") (pin "2") (pintype "passive"))
    )
    (net (code "54") (name "Net-(Q22-DRAIN)") (class "Default")
      (node (ref "Q22") (pin "3") (pinfunction "DRAIN_3") (pintype "passive"))
      (node (ref "R145") (pin "1") (pintype "passive"))
    )
    (net (code "55") (name "Net-(Q22-GATE)") (class "Default")
      (node (ref "Q22") (pin "2") (pinfunction "GATE_2") (pintype "input"))
      (node (ref "Q23") (pin "3") (pinfunction "DRAIN_3") (pintype "passive"))
      (node (ref "R118") (pin "1") (pintype "passive"))
    )
    (net (code "56") (name "Net-(Q23-GATE)") (class "Default")
      (node (ref "C94") (pin "1") (pinfunction "1_1") (pintype "passive"))
      (node (ref "Q23") (pin "2") (pinfunction "GATE_2") (pintype "input"))
      (node (ref "R120") (pin "2") (pintype "passive"))
    )
    (net (code "57") (name "Net-(SW1-B1)") (class "Default")
      (node (ref "R90") (pin "2") (pintype "passive"))
      (node (ref "SW1") (pin "8") (pinfunction "B1_8") (pintype "passive"))
    )
    (net (code "58") (name "Net-(SW1-B2)") (class "Default")
      (node (ref "R100") (pin "2") (pintype "passive"))
      (node (ref "SW1") (pin "7") (pinfunction "B2_7") (pintype "passive"))
    )
    (net (code "59") (name "Net-(SW1-B3)") (class "Default")
      (node (ref "R91") (pin "2") (pintype "passive"))
      (node (ref "SW1") (pin "6") (pinfunction "B3_6") (pintype "passive"))
    )
    (net (code "60") (name "Net-(SW1-B4)") (class "Default")
      (node (ref "R163") (pin "1") (pintype "passive"))
      (node (ref "SW1") (pin "5") (pinfunction "B4_5") (pintype "passive"))
    )
    (net (code "61") (name "Net-(U19-NC~{{slash}DCD_ECI}{slash}VPP)") (class "Default")
      (node (ref "C91") (pin "1") (pinfunction "1_1") (pintype "passive"))
      (node (ref "U19") (pin "16") (pinfunction "NC~{/DCD_ECI}/VPP_16") (pintype "input"))
    )
    (net (code "62") (name "Net-(U19-~{RST})") (class "Default")
      (node (ref "R92") (pin "1") (pintype "passive"))
      (node (ref "U19") (pin "9") (pinfunction "~{RST}_9") (pintype "bidirectional"))
    )
    (net (code "63") (name "Net-(U21-OUT)") (class "Default")
      (node (ref "R200") (pin "1") (pintype "passive"))
      (node (ref "U21") (pin "5") (pinfunction "OUT_5") (pintype "passive"))
    )
    (net (code "64") (name "Net-(U21-SCL)") (class "Default")
      (node (ref "R202") (pin "2") (pintype "passive"))
      (node (ref "U21") (pin "3") (pinfunction "SCL_3") (pintype "passive"))
    )
    (net (code "65") (name "Net-(U21-SDA)") (class "Default")
      (node (ref "R203") (pin "2") (pintype "passive"))
      (node (ref "U21") (pin "4") (pinfunction "SDA_4") (pintype "passive"))
    )
    (net (code "66") (name "Net-(U21-VCC)") (class "Default")
      (node (ref "C143") (pin "1") (pinfunction "1_1") (pintype "passive"))
      (node (ref "C144") (pin "1") (pinfunction "1_1") (pintype "passive"))
      (node (ref "R198") (pin "1") (pintype "passive"))
      (node (ref "U21") (pin "1") (pinfunction "VCC_1") (pintype "power_in"))
    )
    (net (code "67") (name "V3V3") (class "Default")
      (node (ref "C92") (pin "1") (pinfunction "1_1") (pintype "passive"))
      (node (ref "D38") (pin "A") (pinfunction "A_A") (pintype "passive"))
      (node (ref "Q21") (pin "2") (pinfunction "SOURCE_2") (pintype "passive"))
      (node (ref "R100") (pin "1") (pintype "passive"))
      (node (ref "R105") (pin "2") (pintype "passive"))
      (node (ref "R106") (pin "2") (pintype "passive"))
      (node (ref "R108") (pin "2") (pintype "passive"))
      (node (ref "R112") (pin "2") (pintype "passive"))
      (node (ref "R113") (pin "2") (pintype "passive"))
      (node (ref "R116") (pin "1") (pintype "passive"))
      (node (ref "R117") (pin "2") (pintype "passive"))
      (node (ref "R119") (pin "2") (pintype "passive"))
      (node (ref "R201") (pin "2") (pintype "passive"))
      (node (ref "R72") (pin "1") (pintype "passive"))
      (node (ref "R90") (pin "1") (pintype "passive"))
      (node (ref "R91") (pin "1") (pintype "passive"))
    )
    (net (code "68") (name "V3V3_VIO") (class "Default")
      (node (ref "C83") (pin "1") (pinfunction "1_1") (pintype "passive"))
      (node (ref "D37") (pin "1") (pinfunction "ANODE1_1") (pintype "passive"))
      (node (ref "D37") (pin "3") (pinfunction "ANODE2_3") (pintype "passive"))
      (node (ref "R72") (pin "2") (pintype "passive"))
      (node (ref "R73") (pin "2") (pintype "passive"))
      (node (ref "R87") (pin "2") (pintype "passive"))
      (node (ref "R88") (pin "2") (pintype "passive"))
      (node (ref "R92") (pin "2") (pintype "passive"))
      (node (ref "U19") (pin "5") (pinfunction "VIO_5") (pintype "power_in"))
    )
    (net (code "69") (name "VBUS_USB_BDG") (class "Default")
      (node (ref "C86") (pin "1") (pinfunction "1_1") (pintype "passive"))
      (node (ref "C87") (pin "1") (pinfunction "1_1") (pintype "passive"))
      (node (ref "FB5") (pin "2") (pinfunction "2_2") (pintype "passive"))
      (node (ref "U19") (pin "7") (pinfunction "REGIN_7") (pintype "power_in"))
      (node (ref "U19") (pin "8") (pinfunction "VBUS_8") (pintype "input"))
    )
    (net (code "70") (name "VSD_3V3") (class "Default")
      (node (ref "C93") (pin "1") (pinfunction "1_1") (pintype "passive"))
      (node (ref "Q21") (pin "3") (pinfunction "DRAIN_3") (pintype "passive"))
      (node (ref "R116") (pin "2") (pintype "passive"))
      (node (ref "R145") (pin "2") (pintype "passive"))
    )
    (net (code "71") (name "VUSB_REG_3V45") (class "Default")
      (node (ref "C88") (pin "1") (pinfunction "1_1") (pintype "passive"))
      (node (ref "C89") (pin "1") (pinfunction "1_1") (pintype "passive"))
      (node (ref "R73") (pin "1") (pintype "passive"))
      (node (ref "U19") (pin "6") (pinfunction "VDD_6") (pintype "power_in"))
    )
    (net (code "72") (name "unconnected-(J10-ID-Pad4)") (class "Default")
      (node (ref "J10") (pin "4") (pinfunction "ID_4") (pintype "passive+no_connect"))
    )
    (net (code "73") (name "unconnected-(U19-GPIO0_ECI{slash}~{DTR_EC}I-Pad15)") (class "Default")
      (node (ref "U19") (pin "15") (pinfunction "GPIO0_ECI/~{DTR_EC}I_15") (pintype "bidirectional+no_connect"))
    )
    (net (code "74") (name "unconnected-(U19-GPIO0_SCI{slash}~{DCD_SCI}-Pad24)") (class "Default")
      (node (ref "U19") (pin "24") (pinfunction "GPIO0_SCI/~{DCD_SCI}_24") (pintype "bidirectional+no_connect"))
    )
    (net (code "75") (name "unconnected-(U19-GPIO1_ECI{slash}~{DSR_ECI}-Pad14)") (class "Default")
      (node (ref "U19") (pin "14") (pinfunction "GPIO1_ECI/~{DSR_ECI}_14") (pintype "bidirectional+no_connect"))
    )
    (net (code "76") (name "unconnected-(U19-GPIO1_SCI{slash}~{DTR_SCI}-Pad23)") (class "Default")
      (node (ref "U19") (pin "23") (pinfunction "GPIO1_SCI/~{DTR_SCI}_23") (pintype "bidirectional+no_connect"))
    )
    (net (code "77") (name "unconnected-(U19-GPIO2_SCI{slash}~{DSR_SCI}-Pad22)") (class "Default")
      (node (ref "U19") (pin "22") (pinfunction "GPIO2_SCI/~{DSR_SCI}_22") (pintype "bidirectional+no_connect"))
    )
    (net (code "78") (name "unconnected-(U19-~{CTS_ECI}-Pad10)") (class "Default")
      (node (ref "U19") (pin "10") (pinfunction "~{CTS_ECI}_10") (pintype "input+no_connect"))
    )
    (net (code "79") (name "unconnected-(U19-~{CTS_SCI}-Pad18)") (class "Default")
      (node (ref "U19") (pin "18") (pinfunction "~{CTS_SCI}_18") (pintype "input+no_connect"))
    )
    (net (code "80") (name "unconnected-(U19-~{RTS_ECI}-Pad11)") (class "Default")
      (node (ref "U19") (pin "11") (pinfunction "~{RTS_ECI}_11") (pintype "output+no_connect"))
    )
    (net (code "81") (name "unconnected-(U19-~{RTS_SCI}-Pad19)") (class "Default")
      (node (ref "U19") (pin "19") (pinfunction "~{RTS_SCI}_19") (pintype "output+no_connect"))
    )
    (net (code "82") (name "unconnected-(U19-~{SUSPEND{slash}RI_ECI}-Pad17)") (class "Default")
      (node (ref "U19") (pin "17") (pinfunction "~{SUSPEND/RI_ECI}_17") (pintype "bidirectional+no_connect"))
    )
    (net (code "83") (name "unconnected-(U19-~{SUSPEND{slash}RI_SCI}-Pad1)") (class "Default")
      (node (ref "U19") (pin "1") (pinfunction "~{SUSPEND/RI_SCI}_1") (pintype "output+no_connect"))
    )
  )
)
